# CoaxBoard.net
KiCad netlist of a schematic drawn in EAGLE
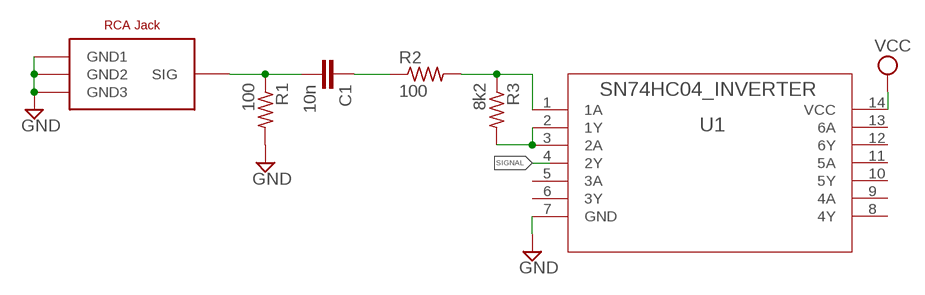
[diagram p0: schematic, sheet 1]

(export (version "E")
  (design (tool "Eeschema 10.0.6"))
  (components
    (comp (ref "C1")
      (value "10n")
      (footprint "eagle-import:C0805")
      (libsource (lib "eagle-import") (part "C-EUC0805"))
    )
    (comp (ref "R1")
      (value "100")
      (footprint "eagle-import:R0805")
      (libsource (lib "eagle-import") (part "R-US_R0805"))
    )
    (comp (ref "R2")
      (value "100")
      (footprint "eagle-import:R0805")
      (libsource (lib "eagle-import") (part "R-US_R0805"))
    )
    (comp (ref "R3")
      (value "8k2")
      (footprint "eagle-import:R0805")
      (libsource (lib "eagle-import") (part "R-US_R0805"))
    )
    (comp (ref "U$1")
      (value "RCA_JACK")
      (footprint "eagle-import:RCA_JACK")
      (libsource (lib "eagle-import") (part "RCA_JACK"))
    )
    (comp (ref "U1")
      (value "SN74HC04_INVERTER")
      (footprint "eagle-import:NS14")
      (fields
        (field (name "GENERIC_PART_NUMBER") "SN74HC04")
        (field (name "MANUFACTURER") "Texas Instruments")
      )
      (libsource (lib "eagle-import") (part "SN74HC04_INVERTER"))
    )
  )
  (nets
    (net (code "1") (name "GND") (class "Default")
      (node (ref "R1") (pin "2") (pinfunction "2_2") (pintype "passive"))
      (node (ref "U$1") (pin "GND1") (pinfunction "GND1_GND1") (pintype "bidirectional"))
      (node (ref "U$1") (pin "GND2") (pinfunction "GND2_GND2") (pintype "bidirectional"))
      (node (ref "U$1") (pin "GND3") (pinfunction "GND3_GND3") (pintype "bidirectional"))
      (node (ref "U1") (pin "7") (pinfunction "GND_7") (pintype "power_in"))
    )
    (net (code "2") (name "Net-(C1-Pad1)") (class "Default")
      (node (ref "C1") (pin "1") (pinfunction "1_1") (pintype "passive"))
      (node (ref "R2") (pin "1") (pinfunction "1_1") (pintype "passive"))
    )
    (net (code "3") (name "Net-(C1-Pad2)") (class "Default")
      (node (ref "C1") (pin "2") (pinfunction "2_2") (pintype "passive"))
      (node (ref "R1") (pin "1") (pinfunction "1_1") (pintype "passive"))
      (node (ref "U$1") (pin "SIG") (pinfunction "SIG_SIG") (pintype "bidirectional"))
    )
    (net (code "4") (name "Net-(U1-1A)") (class "Default")
      (node (ref "R2") (pin "2") (pinfunction "2_2") (pintype "passive"))
      (node (ref "R3") (pin "1") (pinfunction "1_1") (pintype "passive"))
      (node (ref "U1") (pin "1") (pinfunction "1A_1") (pintype "input"))
    )
    (net (code "5") (name "Net-(U1-1Y)") (class "Default")
      (node (ref "R3") (pin "2") (pinfunction "2_2") (pintype "passive"))
      (node (ref "U1") (pin "2") (pinfunction "1Y_2") (pintype "output"))
      (node (ref "U1") (pin "3") (pinfunction "2A_3") (pintype "input"))
    )
    (net (code "6") (name "SIGNAL") (class "Default")
      (node (ref "U1") (pin "4") (pinfunction "2Y_4") (pintype "output"))
    )
    (net (code "7") (name "VCC") (class "Default")
      (node (ref "U1") (pin "14") (pinfunction "VCC_14") (pintype "power_in"))
    )
    (net (code "8") (name "unconnected-(U1-3A-Pad5)") (class "Default")
      (node (ref "U1") (pin "5") (pinfunction "3A_5") (pintype "input"))
    )
    (net (code "9") (name "unconnected-(U1-3Y-Pad6)") (class "Default")
      (node (ref "U1") (pin "6") (pinfunction "3Y_6") (pintype "output"))
    )
    (net (code "10") (name "unconnected-(U1-4A-Pad9)") (class "Default")
      (node (ref "U1") (pin "9") (pinfunction "4A_9") (pintype "input"))
    )
    (net (code "11") (name "unconnected-(U1-4Y-Pad8)") (class "Default")
      (node (ref "U1") (pin "8") (pinfunction "4Y_8") (pintype "output"))
    )
    (net (code "12") (name "unconnected-(U1-5A-Pad11)") (class "Default")
      (node (ref "U1") (pin "11") (pinfunction "5A_11") (pintype "input"))
    )
    (net (code "13") (name "unconnected-(U1-5Y-Pad10)") (class "Default")
      (node (ref "U1") (pin "10") (pinfunction "5Y_10") (pintype "output"))
    )
    (net (code "14") (name "unconnected-(U1-6A-Pad13)") (class "Default")
      (node (ref "U1") (pin "13") (pinfunction "6A_13") (pintype "input"))
    )
    (net (code "15") (name "unconnected-(U1-6Y-Pad12)") (class "Default")
      (node (ref "U1") (pin "12") (pinfunction "6Y_12") (pintype "output"))
    )
  )
)
